# stoichea_v0_2.net
KiCad netlist of a schematic drawn in EAGLE
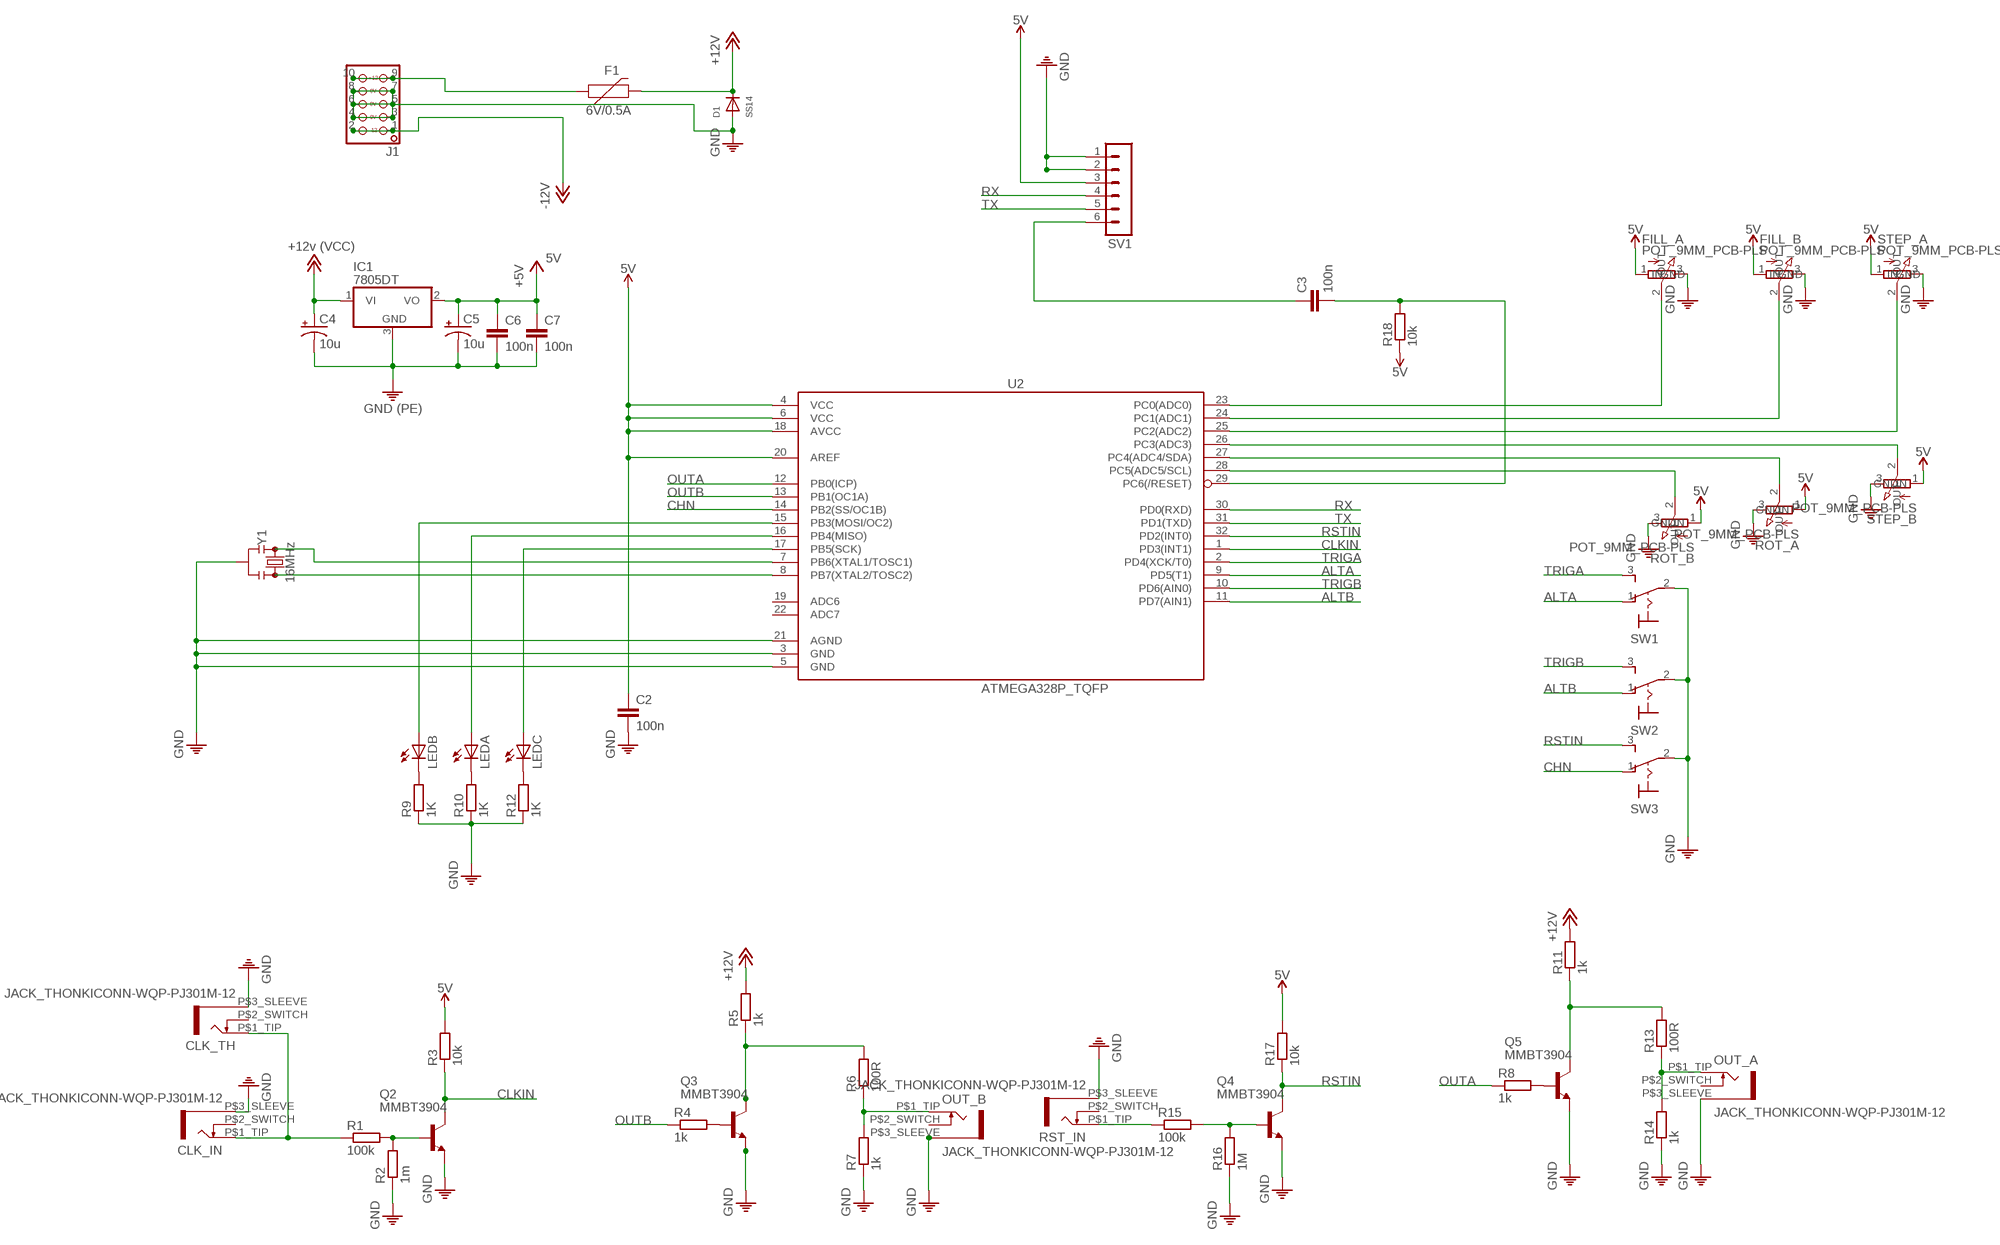
[diagram p0: schematic, sheet 1]

(export (version "E")
  (design (tool "Eeschema 10.0.6"))
  (components
    (comp (ref "C2")
      (value "100n")
      (footprint "eagle-import:C0603")
      (libsource (lib "eagle-import") (part "CAPACITOR-EUC0603"))
    )
    (comp (ref "C3")
      (value "100n")
      (footprint "eagle-import:C0603K")
      (libsource (lib "eagle-import") (part "CAPACITOR-EUC0603K"))
    )
    (comp (ref "C4")
      (value "10u")
      (footprint "eagle-import:PANASONIC_B")
      (libsource (lib "eagle-import") (part "CAPACITOR_POLARIZED-USB"))
    )
    (comp (ref "C5")
      (value "10u")
      (footprint "eagle-import:PANASONIC_B")
      (libsource (lib "eagle-import") (part "CAPACITOR_POLARIZED-USB"))
    )
    (comp (ref "C6")
      (value "100n")
      (footprint "eagle-import:C0603")
      (libsource (lib "eagle-import") (part "CAPACITOR-EUC0603"))
    )
    (comp (ref "C7")
      (value "100n")
      (footprint "eagle-import:C0603")
      (libsource (lib "eagle-import") (part "CAPACITOR-EUC0603"))
    )
    (comp (ref "CLK_IN")
      (value "JACK_THONKICONN-WQP-PJ301M-12")
      (footprint "eagle-import:WQP-PJ301M-12_JACK")
      (libsource (lib "eagle-import") (part "JACK_THONKICONN-WQP-PJ301M-12"))
    )
    (comp (ref "CLK_TH")
      (value "JACK_THONKICONN-WQP-PJ301M-12")
      (footprint "eagle-import:WQP-PJ301M-12_JACK")
      (libsource (lib "eagle-import") (part "JACK_THONKICONN-WQP-PJ301M-12"))
    )
    (comp (ref "D1")
      (value "SS14")
      (footprint "eagle-import:SOD-323F")
      (libsource (lib "eagle-import") (part "DIODESOD-323F"))
    )
    (comp (ref "F1")
      (value "6V/0.5A")
      (footprint "eagle-import:1206")
      (libsource (lib "eagle-import") (part "FUSE-PPTC_HALF-AMP"))
    )
    (comp (ref "FILL_A")
      (value "POT_9MM_PCB-PLS")
      (footprint "eagle-import:9MM_PLS")
      (libsource (lib "eagle-import") (part "POT_9MM_PCB-PLS"))
    )
    (comp (ref "FILL_B")
      (value "POT_9MM_PCB-PLS")
      (footprint "eagle-import:9MM_PLS")
      (libsource (lib "eagle-import") (part "POT_9MM_PCB-PLS"))
    )
    (comp (ref "IC1")
      (value "7805DT")
      (footprint "eagle-import:TO252")
      (libsource (lib "eagle-import") (part "78DT05"))
    )
    (comp (ref "J1")
      (value "HEADER-EUROPWR_2X05-OPEN")
      (footprint "eagle-import:2X05_EUROPWR_OPEN")
      (libsource (lib "eagle-import") (part "HEADER-EUROPWR_2X05-OPEN"))
    )
    (comp (ref "LEDA")
      (value "LED3MM")
      (footprint "eagle-import:LED3MM")
      (libsource (lib "eagle-import") (part "LED3MM"))
    )
    (comp (ref "LEDB")
      (value "LED3MM")
      (footprint "eagle-import:LED3MM")
      (libsource (lib "eagle-import") (part "LED3MM"))
    )
    (comp (ref "LEDC")
      (value "LED3MM")
      (footprint "eagle-import:LED3MM")
      (libsource (lib "eagle-import") (part "LED3MM"))
    )
    (comp (ref "OUT_A")
      (value "JACK_THONKICONN-WQP-PJ301M-12")
      (footprint "eagle-import:WQP-PJ301M-12_JACK")
      (libsource (lib "eagle-import") (part "JACK_THONKICONN-WQP-PJ301M-12"))
    )
    (comp (ref "OUT_B")
      (value "JACK_THONKICONN-WQP-PJ301M-12")
      (footprint "eagle-import:WQP-PJ301M-12_JACK")
      (libsource (lib "eagle-import") (part "JACK_THONKICONN-WQP-PJ301M-12"))
    )
    (comp (ref "Q2")
      (value "MMBT3904")
      (footprint "eagle-import:SOT23-BEC")
      (libsource (lib "eagle-import") (part "TRANSISTOR-NPN-SOT23-BECMMBT3904LT1"))
    )
    (comp (ref "Q3")
      (value "MMBT3904")
      (footprint "eagle-import:SOT23-BEC")
      (libsource (lib "eagle-import") (part "TRANSISTOR-NPN-SOT23-BECMMBT3904LT1"))
    )
    (comp (ref "Q4")
      (value "MMBT3904")
      (footprint "eagle-import:SOT23-BEC")
      (libsource (lib "eagle-import") (part "TRANSISTOR-NPN-SOT23-BECMMBT3904LT1"))
    )
    (comp (ref "Q5")
      (value "MMBT3904")
      (footprint "eagle-import:SOT23-BEC")
      (libsource (lib "eagle-import") (part "TRANSISTOR-NPN-SOT23-BECMMBT3904LT1"))
    )
    (comp (ref "R1")
      (value "100k")
      (footprint "eagle-import:R0603")
      (libsource (lib "eagle-import") (part "RESISTOR-EU_R0603"))
    )
    (comp (ref "R2")
      (value "1m")
      (footprint "eagle-import:R0603")
      (libsource (lib "eagle-import") (part "RESISTOR-EU_R0603"))
    )
    (comp (ref "R3")
      (value "10k")
      (footprint "eagle-import:R0603")
      (libsource (lib "eagle-import") (part "RESISTOR-EU_R0603"))
    )
    (comp (ref "R4")
      (value "1k")
      (footprint "eagle-import:R0603")
      (libsource (lib "eagle-import") (part "RESISTOR-EU_R0603"))
    )
    (comp (ref "R5")
      (value "1k")
      (footprint "eagle-import:R0603")
      (libsource (lib "eagle-import") (part "RESISTOR-EU_R0603"))
    )
    (comp (ref "R6")
      (value "100R")
      (footprint "eagle-import:R0603")
      (libsource (lib "eagle-import") (part "RESISTOR-EU_R0603"))
    )
    (comp (ref "R7")
      (value "1k")
      (footprint "eagle-import:R0603")
      (libsource (lib "eagle-import") (part "RESISTOR-EU_R0603"))
    )
    (comp (ref "R8")
      (value "1k")
      (footprint "eagle-import:R0603")
      (libsource (lib "eagle-import") (part "RESISTOR-EU_R0603"))
    )
    (comp (ref "R9")
      (value "1K")
      (footprint "eagle-import:R0603")
      (libsource (lib "eagle-import") (part "RESISTOR-EU_R0603"))
    )
    (comp (ref "R10")
      (value "1K")
      (footprint "eagle-import:R0603")
      (libsource (lib "eagle-import") (part "RESISTOR-EU_R0603"))
    )
    (comp (ref "R11")
      (value "1k")
      (footprint "eagle-import:R0603")
      (libsource (lib "eagle-import") (part "RESISTOR-EU_R0603"))
    )
    (comp (ref "R12")
      (value "1K")
      (footprint "eagle-import:R0603")
      (libsource (lib "eagle-import") (part "RESISTOR-EU_R0603"))
    )
    (comp (ref "R13")
      (value "100R")
      (footprint "eagle-import:R0603")
      (libsource (lib "eagle-import") (part "RESISTOR-EU_R0603"))
    )
    (comp (ref "R14")
      (value "1k")
      (footprint "eagle-import:R0603")
      (libsource (lib "eagle-import") (part "RESISTOR-EU_R0603"))
    )
    (comp (ref "R15")
      (value "100k")
      (footprint "eagle-import:R0603")
      (libsource (lib "eagle-import") (part "RESISTOR-EU_R0603"))
    )
    (comp (ref "R16")
      (value "1M")
      (footprint "eagle-import:R0603")
      (libsource (lib "eagle-import") (part "RESISTOR-EU_R0603"))
    )
    (comp (ref "R17")
      (value "10k")
      (footprint "eagle-import:R0603")
      (libsource (lib "eagle-import") (part "RESISTOR-EU_R0603"))
    )
    (comp (ref "R18")
      (value "10k")
      (footprint "eagle-import:R0603")
      (libsource (lib "eagle-import") (part "RESISTOR-EU_R0603"))
    )
    (comp (ref "ROT_A")
      (value "POT_9MM_PCB-PLS")
      (footprint "eagle-import:9MM_PLS")
      (libsource (lib "eagle-import") (part "POT_9MM_PCB-PLS"))
    )
    (comp (ref "ROT_B")
      (value "POT_9MM_PCB-PLS")
      (footprint "eagle-import:9MM_PLS")
      (libsource (lib "eagle-import") (part "POT_9MM_PCB-PLS"))
    )
    (comp (ref "RST_IN")
      (value "JACK_THONKICONN-WQP-PJ301M-12")
      (footprint "eagle-import:WQP-PJ301M-12_JACK")
      (libsource (lib "eagle-import") (part "JACK_THONKICONN-WQP-PJ301M-12"))
    )
    (comp (ref "STEP_A")
      (value "POT_9MM_PCB-PLS")
      (footprint "eagle-import:9MM_PLS")
      (libsource (lib "eagle-import") (part "POT_9MM_PCB-PLS"))
    )
    (comp (ref "STEP_B")
      (value "POT_9MM_PCB-PLS")
      (footprint "eagle-import:9MM_PLS")
      (libsource (lib "eagle-import") (part "POT_9MM_PCB-PLS"))
    )
    (comp (ref "SV1")
      (value "MA06-1")
      (footprint "eagle-import:MA06-1")
      (libsource (lib "eagle-import") (part "MA06-1"))
    )
    (comp (ref "SW1")
      (value "SWITCH-SPDT-320-916")
      (footprint "eagle-import:320-916")
      (libsource (lib "eagle-import") (part "SWITCH-SPDT-320-916"))
    )
    (comp (ref "SW2")
      (value "SWITCH-SPDT-320-916")
      (footprint "eagle-import:320-916")
      (libsource (lib "eagle-import") (part "SWITCH-SPDT-320-916"))
    )
    (comp (ref "SW3")
      (value "SWITCH-SPDT-320-916")
      (footprint "eagle-import:320-916")
      (libsource (lib "eagle-import") (part "SWITCH-SPDT-320-916"))
    )
    (comp (ref "U2")
      (value "ATMEGA328P_TQFP")
      (footprint "eagle-import:TQFP32-08")
      (libsource (lib "eagle-import") (part "ATMEGA328P_TQFP"))
    )
    (comp (ref "Y1")
      (value "16MHz")
      (footprint "eagle-import:RESONATOR-SMD-3.2X1.3")
      (libsource (lib "eagle-import") (part "RESONATORSMD-3.2X1.3"))
    )
  )
  (nets
    (net (code "1") (name "+5V") (class "Default")
      (node (ref "C2") (pin "1") (pinfunction "1_1") (pintype "passive"))
      (node (ref "C5") (pin "+") (pinfunction "+_+") (pintype "passive"))
      (node (ref "C6") (pin "1") (pinfunction "1_1") (pintype "passive"))
      (node (ref "C7") (pin "1") (pinfunction "1_1") (pintype "passive"))
      (node (ref "FILL_A") (pin "1") (pinfunction "GND_1") (pintype "passive"))
      (node (ref "FILL_B") (pin "1") (pinfunction "GND_1") (pintype "passive"))
      (node (ref "IC1") (pin "2") (pinfunction "VO_2") (pintype "passive"))
      (node (ref "R17") (pin "2") (pinfunction "2_2") (pintype "passive"))
      (node (ref "R18") (pin "1") (pinfunction "1_1") (pintype "passive"))
      (node (ref "R3") (pin "2") (pinfunction "2_2") (pintype "passive"))
      (node (ref "ROT_A") (pin "1") (pinfunction "GND_1") (pintype "passive"))
      (node (ref "ROT_B") (pin "1") (pinfunction "GND_1") (pintype "passive"))
      (node (ref "STEP_A") (pin "1") (pinfunction "GND_1") (pintype "passive"))
      (node (ref "STEP_B") (pin "1") (pinfunction "GND_1") (pintype "passive"))
      (node (ref "SV1") (pin "3") (pinfunction "3_3") (pintype "passive"))
      (node (ref "U2") (pin "18") (pinfunction "AVCC_18") (pintype "bidirectional"))
      (node (ref "U2") (pin "20") (pinfunction "AREF_20") (pintype "bidirectional"))
      (node (ref "U2") (pin "4") (pinfunction "VCC_4") (pintype "bidirectional"))
      (node (ref "U2") (pin "6") (pinfunction "VCC_6") (pintype "bidirectional"))
    )
    (net (code "2") (name "+12V") (class "Default")
      (node (ref "C4") (pin "+") (pinfunction "+_+") (pintype "passive"))
      (node (ref "D1") (pin "C") (pinfunction "C_C") (pintype "passive"))
      (node (ref "F1") (pin "2") (pinfunction "2_2") (pintype "bidirectional"))
      (node (ref "IC1") (pin "1") (pinfunction "VI_1") (pintype "input"))
      (node (ref "R11") (pin "2") (pinfunction "2_2") (pintype "passive"))
      (node (ref "R5") (pin "2") (pinfunction "2_2") (pintype "passive"))
    )
    (net (code "3") (name "-12V") (class "Default")
      (node (ref "J1") (pin "1") (pinfunction "1_1") (pintype "passive"))
      (node (ref "J1") (pin "2") (pinfunction "2_2") (pintype "passive"))
    )
    (net (code "4") (name "/ALTA") (class "Default")
      (node (ref "SW1") (pin "1") (pinfunction "O_1") (pintype "passive"))
      (node (ref "U2") (pin "9") (pinfunction "PD5(T1)_9") (pintype "bidirectional"))
    )
    (net (code "5") (name "/ALTB") (class "Default")
      (node (ref "SW2") (pin "1") (pinfunction "O_1") (pintype "passive"))
      (node (ref "U2") (pin "11") (pinfunction "PD7(AIN1)_11") (pintype "bidirectional"))
    )
    (net (code "6") (name "/CHN") (class "Default")
      (node (ref "SW3") (pin "1") (pinfunction "O_1") (pintype "passive"))
      (node (ref "U2") (pin "14") (pinfunction "PB2(SS/OC1B)_14") (pintype "bidirectional"))
    )
    (net (code "7") (name "/CLKIN") (class "Default")
      (node (ref "Q2") (pin "C") (pinfunction "C_C") (pintype "passive"))
      (node (ref "R3") (pin "1") (pinfunction "1_1") (pintype "passive"))
      (node (ref "U2") (pin "1") (pinfunction "PD3(INT1)_1") (pintype "bidirectional"))
    )
    (net (code "8") (name "/OUTA") (class "Default")
      (node (ref "R8") (pin "1") (pinfunction "1_1") (pintype "passive"))
      (node (ref "U2") (pin "12") (pinfunction "PB0(ICP)_12") (pintype "bidirectional"))
    )
    (net (code "9") (name "/OUTB") (class "Default")
      (node (ref "R4") (pin "1") (pinfunction "1_1") (pintype "passive"))
      (node (ref "U2") (pin "13") (pinfunction "PB1(OC1A)_13") (pintype "bidirectional"))
    )
    (net (code "10") (name "/RSTIN") (class "Default")
      (node (ref "Q4") (pin "C") (pinfunction "C_C") (pintype "passive"))
      (node (ref "R17") (pin "1") (pinfunction "1_1") (pintype "passive"))
      (node (ref "SW3") (pin "3") (pinfunction "S_3") (pintype "passive"))
      (node (ref "U2") (pin "32") (pinfunction "PD2(INT0)_32") (pintype "bidirectional"))
    )
    (net (code "11") (name "/RX") (class "Default")
      (node (ref "SV1") (pin "4") (pinfunction "4_4") (pintype "passive"))
      (node (ref "U2") (pin "30") (pinfunction "PD0(RXD)_30") (pintype "bidirectional"))
    )
    (net (code "12") (name "/TRIGA") (class "Default")
      (node (ref "SW1") (pin "3") (pinfunction "S_3") (pintype "passive"))
      (node (ref "U2") (pin "2") (pinfunction "PD4(XCK/T0)_2") (pintype "bidirectional"))
    )
    (net (code "13") (name "/TRIGB") (class "Default")
      (node (ref "SW2") (pin "3") (pinfunction "S_3") (pintype "passive"))
      (node (ref "U2") (pin "10") (pinfunction "PD6(AIN0)_10") (pintype "bidirectional"))
    )
    (net (code "14") (name "/TX") (class "Default")
      (node (ref "SV1") (pin "5") (pinfunction "5_5") (pintype "passive"))
      (node (ref "U2") (pin "31") (pinfunction "PD1(TXD)_31") (pintype "bidirectional"))
    )
    (net (code "15") (name "GND") (class "Default")
      (node (ref "C2") (pin "2") (pinfunction "2_2") (pintype "passive"))
      (node (ref "C4") (pin "-") (pinfunction "-_-") (pintype "passive"))
      (node (ref "C5") (pin "-") (pinfunction "-_-") (pintype "passive"))
      (node (ref "C6") (pin "2") (pinfunction "2_2") (pintype "passive"))
      (node (ref "C7") (pin "2") (pinfunction "2_2") (pintype "passive"))
      (node (ref "CLK_IN") (pin "P$3_SLEEVE") (pinfunction "1_P$3_SLEEVE") (pintype "passive"))
      (node (ref "CLK_TH") (pin "P$3_SLEEVE") (pinfunction "1_P$3_SLEEVE") (pintype "passive"))
      (node (ref "D1") (pin "A") (pinfunction "A_A") (pintype "passive"))
      (node (ref "FILL_A") (pin "3") (pinfunction "IN_3") (pintype "passive"))
      (node (ref "FILL_B") (pin "3") (pinfunction "IN_3") (pintype "passive"))
      (node (ref "IC1") (pin "3") (pinfunction "GND_3") (pintype "passive"))
      (node (ref "J1") (pin "3") (pinfunction "3_3") (pintype "passive"))
      (node (ref "J1") (pin "4") (pinfunction "4_4") (pintype "passive"))
      (node (ref "J1") (pin "5") (pinfunction "5_5") (pintype "passive"))
      (node (ref "J1") (pin "6") (pinfunction "6_6") (pintype "passive"))
      (node (ref "J1") (pin "7") (pinfunction "7_7") (pintype "passive"))
      (node (ref "J1") (pin "8") (pinfunction "8_8") (pintype "passive"))
      (node (ref "OUT_A") (pin "P$3_SLEEVE") (pinfunction "1_P$3_SLEEVE") (pintype "passive"))
      (node (ref "OUT_B") (pin "P$3_SLEEVE") (pinfunction "1_P$3_SLEEVE") (pintype "passive"))
      (node (ref "Q2") (pin "E") (pinfunction "E_E") (pintype "passive"))
      (node (ref "Q3") (pin "E") (pinfunction "E_E") (pintype "passive"))
      (node (ref "Q4") (pin "E") (pinfunction "E_E") (pintype "passive"))
      (node (ref "Q5") (pin "E") (pinfunction "E_E") (pintype "passive"))
      (node (ref "R10") (pin "1") (pinfunction "1_1") (pintype "passive"))
      (node (ref "R12") (pin "1") (pinfunction "1_1") (pintype "passive"))
      (node (ref "R14") (pin "1") (pinfunction "1_1") (pintype "passive"))
      (node (ref "R16") (pin "1") (pinfunction "1_1") (pintype "passive"))
      (node (ref "R2") (pin "1") (pinfunction "1_1") (pintype "passive"))
      (node (ref "R7") (pin "1") (pinfunction "1_1") (pintype "passive"))
      (node (ref "R9") (pin "1") (pinfunction "1_1") (pintype "passive"))
      (node (ref "ROT_A") (pin "3") (pinfunction "IN_3") (pintype "passive"))
      (node (ref "ROT_B") (pin "3") (pinfunction "IN_3") (pintype "passive"))
      (node (ref "RST_IN") (pin "P$3_SLEEVE") (pinfunction "1_P$3_SLEEVE") (pintype "passive"))
      (node (ref "STEP_A") (pin "3") (pinfunction "IN_3") (pintype "passive"))
      (node (ref "STEP_B") (pin "3") (pinfunction "IN_3") (pintype "passive"))
      (node (ref "SV1") (pin "1") (pinfunction "1_1") (pintype "passive"))
      (node (ref "SV1") (pin "2") (pinfunction "2_2") (pintype "passive"))
      (node (ref "SW1") (pin "2") (pinfunction "P_2") (pintype "passive"))
      (node (ref "SW2") (pin "2") (pinfunction "P_2") (pintype "passive"))
      (node (ref "SW3") (pin "2") (pinfunction "P_2") (pintype "passive"))
      (node (ref "U2") (pin "21") (pinfunction "AGND_21") (pintype "bidirectional"))
      (node (ref "U2") (pin "3") (pinfunction "GND_3") (pintype "bidirectional"))
      (node (ref "U2") (pin "5") (pinfunction "GND_5") (pintype "bidirectional"))
      (node (ref "Y1") (pin "2") (pinfunction "2_2") (pintype "passive"))
    )
    (net (code "16") (name "Net-(C3-Pad1)") (class "Default")
      (node (ref "C3") (pin "1") (pinfunction "1_1") (pintype "passive"))
      (node (ref "SV1") (pin "6") (pinfunction "6_6") (pintype "passive"))
    )
    (net (code "17") (name "Net-(CLK_IN-2)") (class "Default")
      (node (ref "CLK_IN") (pin "P$1_TIP") (pinfunction "2_P$1_TIP") (pintype "passive"))
      (node (ref "CLK_TH") (pin "P$1_TIP") (pinfunction "2_P$1_TIP") (pintype "passive"))
      (node (ref "R1") (pin "1") (pinfunction "1_1") (pintype "passive"))
    )
    (net (code "18") (name "Net-(F1-Pad1)") (class "Default")
      (node (ref "F1") (pin "1") (pinfunction "1_1") (pintype "bidirectional"))
      (node (ref "J1") (pin "10") (pinfunction "10_10") (pintype "passive"))
      (node (ref "J1") (pin "9") (pinfunction "9_9") (pintype "passive"))
    )
    (net (code "19") (name "Net-(FILL_A-OUT)") (class "Default")
      (node (ref "FILL_A") (pin "2") (pinfunction "OUT_2") (pintype "passive"))
      (node (ref "U2") (pin "23") (pinfunction "PC0(ADC0)_23") (pintype "bidirectional"))
    )
    (net (code "20") (name "Net-(FILL_B-OUT)") (class "Default")
      (node (ref "FILL_B") (pin "2") (pinfunction "OUT_2") (pintype "passive"))
      (node (ref "U2") (pin "24") (pinfunction "PC1(ADC1)_24") (pintype "bidirectional"))
    )
    (net (code "21") (name "Net-(LEDA-C)") (class "Default")
      (node (ref "LEDA") (pin "K") (pinfunction "C_K") (pintype "passive"))
      (node (ref "R10") (pin "2") (pinfunction "2_2") (pintype "passive"))
    )
    (net (code "22") (name "Net-(LEDB-C)") (class "Default")
      (node (ref "LEDB") (pin "K") (pinfunction "C_K") (pintype "passive"))
      (node (ref "R9") (pin "2") (pinfunction "2_2") (pintype "passive"))
    )
    (net (code "23") (name "Net-(LEDC-C)") (class "Default")
      (node (ref "LEDC") (pin "K") (pinfunction "C_K") (pintype "passive"))
      (node (ref "R12") (pin "2") (pinfunction "2_2") (pintype "passive"))
    )
    (net (code "24") (name "Net-(OUT_A-2)") (class "Default")
      (node (ref "OUT_A") (pin "P$1_TIP") (pinfunction "2_P$1_TIP") (pintype "passive"))
      (node (ref "R13") (pin "1") (pinfunction "1_1") (pintype "passive"))
      (node (ref "R14") (pin "2") (pinfunction "2_2") (pintype "passive"))
    )
    (net (code "25") (name "Net-(OUT_B-2)") (class "Default")
      (node (ref "OUT_B") (pin "P$1_TIP") (pinfunction "2_P$1_TIP") (pintype "passive"))
      (node (ref "R6") (pin "1") (pinfunction "1_1") (pintype "passive"))
      (node (ref "R7") (pin "2") (pinfunction "2_2") (pintype "passive"))
    )
    (net (code "26") (name "Net-(Q2-PadB)") (class "Default")
      (node (ref "Q2") (pin "B") (pinfunction "B_B") (pintype "passive"))
      (node (ref "R1") (pin "2") (pinfunction "2_2") (pintype "passive"))
      (node (ref "R2") (pin "2") (pinfunction "2_2") (pintype "passive"))
    )
    (net (code "27") (name "Net-(Q3-PadB)") (class "Default")
      (node (ref "Q3") (pin "B") (pinfunction "B_B") (pintype "passive"))
      (node (ref "R4") (pin "2") (pinfunction "2_2") (pintype "passive"))
    )
    (net (code "28") (name "Net-(Q3-PadC)") (class "Default")
      (node (ref "Q3") (pin "C") (pinfunction "C_C") (pintype "passive"))
      (node (ref "R5") (pin "1") (pinfunction "1_1") (pintype "passive"))
      (node (ref "R6") (pin "2") (pinfunction "2_2") (pintype "passive"))
    )
    (net (code "29") (name "Net-(Q4-PadB)") (class "Default")
      (node (ref "Q4") (pin "B") (pinfunction "B_B") (pintype "passive"))
      (node (ref "R15") (pin "2") (pinfunction "2_2") (pintype "passive"))
      (node (ref "R16") (pin "2") (pinfunction "2_2") (pintype "passive"))
    )
    (net (code "30") (name "Net-(Q5-PadB)") (class "Default")
      (node (ref "Q5") (pin "B") (pinfunction "B_B") (pintype "passive"))
      (node (ref "R8") (pin "2") (pinfunction "2_2") (pintype "passive"))
    )
    (net (code "31") (name "Net-(Q5-PadC)") (class "Default")
      (node (ref "Q5") (pin "C") (pinfunction "C_C") (pintype "passive"))
      (node (ref "R11") (pin "1") (pinfunction "1_1") (pintype "passive"))
      (node (ref "R13") (pin "2") (pinfunction "2_2") (pintype "passive"))
    )
    (net (code "32") (name "Net-(ROT_A-OUT)") (class "Default")
      (node (ref "ROT_A") (pin "2") (pinfunction "OUT_2") (pintype "passive"))
      (node (ref "U2") (pin "27") (pinfunction "PC4(ADC4/SDA)_27") (pintype "bidirectional"))
    )
    (net (code "33") (name "Net-(ROT_B-OUT)") (class "Default")
      (node (ref "ROT_B") (pin "2") (pinfunction "OUT_2") (pintype "passive"))
      (node (ref "U2") (pin "28") (pinfunction "PC5(ADC5/SCL)_28") (pintype "bidirectional"))
    )
    (net (code "34") (name "Net-(RST_IN-2)") (class "Default")
      (node (ref "R15") (pin "1") (pinfunction "1_1") (pintype "passive"))
      (node (ref "RST_IN") (pin "P$1_TIP") (pinfunction "2_P$1_TIP") (pintype "passive"))
    )
    (net (code "35") (name "Net-(STEP_A-OUT)") (class "Default")
      (node (ref "STEP_A") (pin "2") (pinfunction "OUT_2") (pintype "passive"))
      (node (ref "U2") (pin "25") (pinfunction "PC2(ADC2)_25") (pintype "bidirectional"))
    )
    (net (code "36") (name "Net-(STEP_B-OUT)") (class "Default")
      (node (ref "STEP_B") (pin "2") (pinfunction "OUT_2") (pintype "passive"))
      (node (ref "U2") (pin "26") (pinfunction "PC3(ADC3)_26") (pintype "bidirectional"))
    )
    (net (code "37") (name "Net-(U2-PB3(MOSI{slash}OC2))") (class "Default")
      (node (ref "LEDB") (pin "A") (pinfunction "A_A") (pintype "passive"))
      (node (ref "U2") (pin "15") (pinfunction "PB3(MOSI/OC2)_15") (pintype "bidirectional"))
    )
    (net (code "38") (name "Net-(U2-PB4(MISO))") (class "Default")
      (node (ref "LEDA") (pin "A") (pinfunction "A_A") (pintype "passive"))
      (node (ref "U2") (pin "16") (pinfunction "PB4(MISO)_16") (pintype "bidirectional"))
    )
    (net (code "39") (name "Net-(U2-PB5(SCK))") (class "Default")
      (node (ref "LEDC") (pin "A") (pinfunction "A_A") (pintype "passive"))
      (node (ref "U2") (pin "17") (pinfunction "PB5(SCK)_17") (pintype "bidirectional"))
    )
    (net (code "40") (name "Net-(U2-PB6(XTAL1{slash}TOSC1))") (class "Default")
      (node (ref "U2") (pin "7") (pinfunction "PB6(XTAL1/TOSC1)_7") (pintype "bidirectional"))
      (node (ref "Y1") (pin "1") (pinfunction "1_1") (pintype "passive"))
    )
    (net (code "41") (name "Net-(U2-PB7(XTAL2{slash}TOSC2))") (class "Default")
      (node (ref "U2") (pin "8") (pinfunction "PB7(XTAL2/TOSC2)_8") (pintype "bidirectional"))
      (node (ref "Y1") (pin "3") (pinfunction "3_3") (pintype "passive"))
    )
    (net (code "42") (name "Net-(U2-PC6({slash}RESET))") (class "Default")
      (node (ref "C3") (pin "2") (pinfunction "2_2") (pintype "passive"))
      (node (ref "R18") (pin "2") (pinfunction "2_2") (pintype "passive"))
      (node (ref "U2") (pin "29") (pinfunction "PC6(/RESET)_29") (pintype "bidirectional"))
    )
    (net (code "43") (name "unconnected-(CLK_IN-3-PadP$2_SWITCH)") (class "Default")
      (node (ref "CLK_IN") (pin "P$2_SWITCH") (pinfunction "3_P$2_SWITCH") (pintype "passive"))
    )
    (net (code "44") (name "unconnected-(CLK_TH-3-PadP$2_SWITCH)") (class "Default")
      (node (ref "CLK_TH") (pin "P$2_SWITCH") (pinfunction "3_P$2_SWITCH") (pintype "passive"))
    )
    (net (code "45") (name "unconnected-(OUT_A-3-PadP$2_SWITCH)") (class "Default")
      (node (ref "OUT_A") (pin "P$2_SWITCH") (pinfunction "3_P$2_SWITCH") (pintype "passive"))
    )
    (net (code "46") (name "unconnected-(OUT_B-3-PadP$2_SWITCH)") (class "Default")
      (node (ref "OUT_B") (pin "P$2_SWITCH") (pinfunction "3_P$2_SWITCH") (pintype "passive"))
    )
    (net (code "47") (name "unconnected-(RST_IN-3-PadP$2_SWITCH)") (class "Default")
      (node (ref "RST_IN") (pin "P$2_SWITCH") (pinfunction "3_P$2_SWITCH") (pintype "passive"))
    )
    (net (code "48") (name "unconnected-(U2-ADC6-Pad19)") (class "Default")
      (node (ref "U2") (pin "19") (pinfunction "ADC6_19") (pintype "bidirectional"))
    )
    (net (code "49") (name "unconnected-(U2-ADC7-Pad22)") (class "Default")
      (node (ref "U2") (pin "22") (pinfunction "ADC7_22") (pintype "bidirectional"))
    )
  )
)
